# 1_Power_Connector.net
KiCad netlist of a schematic drawn in Altium Designer
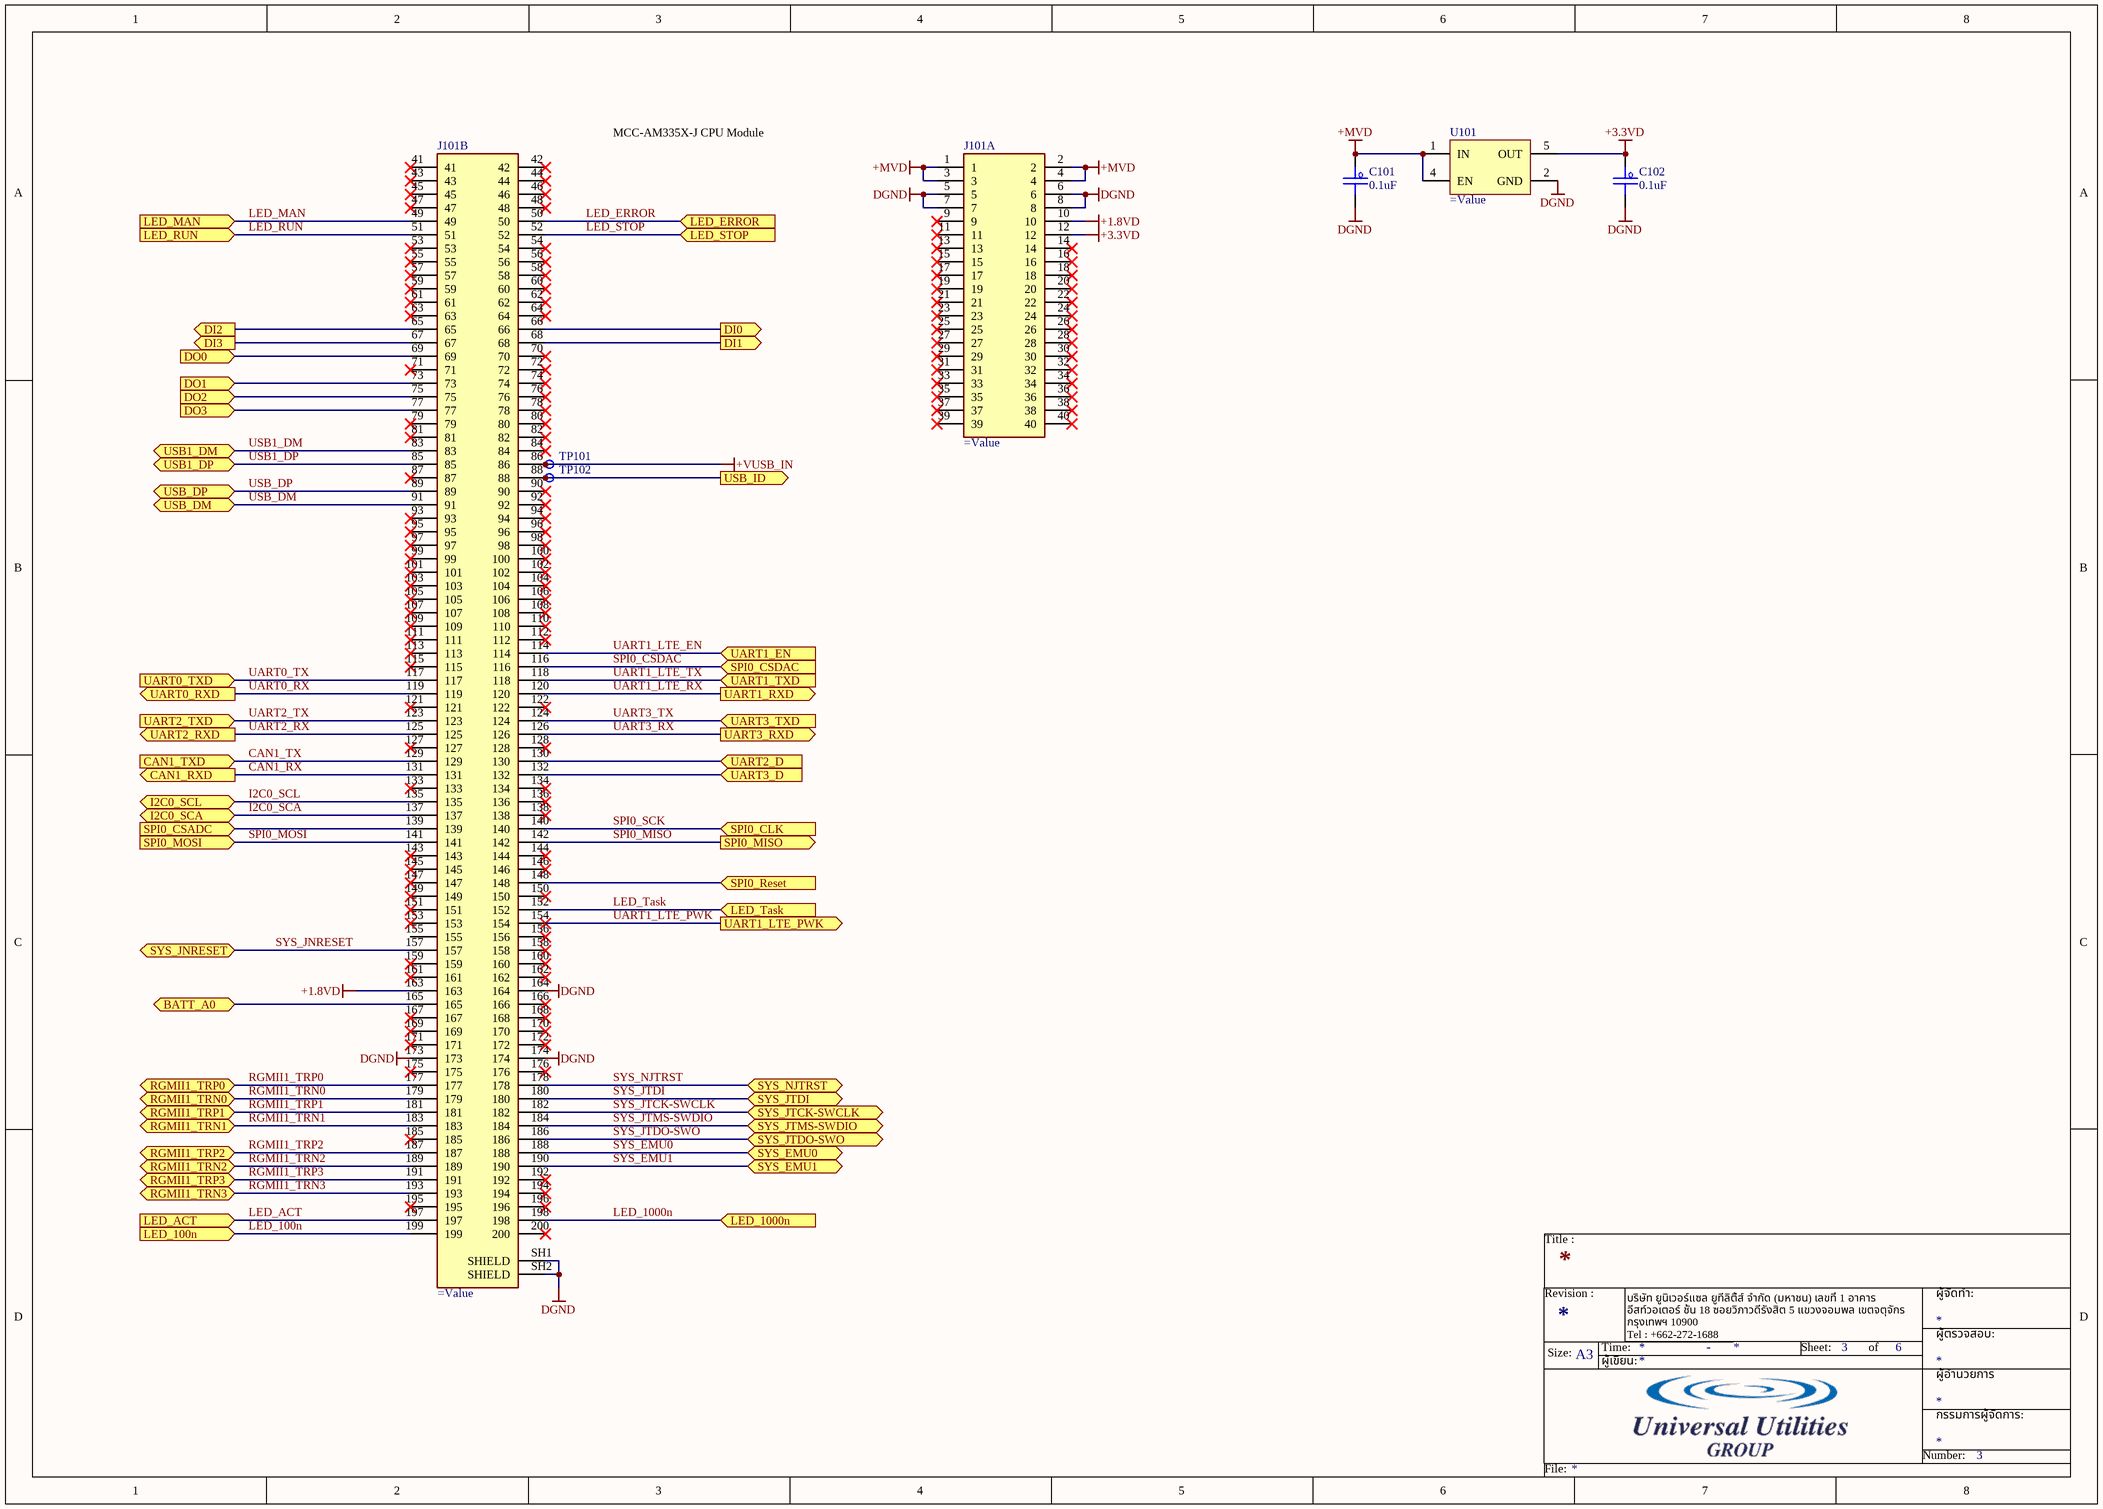
[diagram p0: 1_Power_Connector.SchDoc]

(export (version "E")
  (design (tool "Eeschema 10.0.6"))
  (components
    (comp (ref "C101")
      (value "0.1uF")
      (footprint "C_0603")
      (description "CAP CER 0.1UF 50V X7R 0603")
      (fields (field (name "MANUFACTURER") "KEMET") (field (name "PARTNUMBER") "C0603C104K5RACTU"))
      (libsource (lib "UUSymbol") (part "C_Capacitor"))
    )
    (comp (ref "C102")
      (value "0.1uF")
      (footprint "C_0603")
      (description "CAP CER 0.1UF 50V X7R 0603")
      (fields (field (name "MANUFACTURER") "KEMET") (field (name "PARTNUMBER") "C0603C104K5RACTU"))
      (libsource (lib "UUSymbol") (part "C_Capacitor"))
    )
    (comp (ref "J101")
      (value "~")
      (footprint "DDR2-SO-DIMM")
      (description "CONN SKT SODIMM 200POS R/A SMD")
      (fields
        (field (name "PARTNUMBER") "1473149-4")
        (field (name "MANUFACTURER") "TE Connectivity AMP Connectors")
      )
      (libsource (lib "UUSymbol") (part "CON_DDR2"))
    )
    (comp (ref "TP101")
      (value "~")
      (footprint "TP_Testpoint")
      (description "TestPoint")
      (libsource (lib "UUSymbol") (part "TP_TestPoint"))
    )
    (comp (ref "TP102")
      (value "~")
      (footprint "TP_Testpoint")
      (description "TestPoint")
      (libsource (lib "UUSymbol") (part "TP_TestPoint"))
    )
    (comp (ref "U101")
      (value "~")
      (footprint "SOT95P280X145-5N")
      (description "200mA 360mV@(10mA) Fixed 3.3V~3.3V Positive 1 36V SOT-23-5 Linear Voltage Regulators (LDO) ROHS")
      (fields (field (name "PARTNUMBER") "RT9069-33GB") (field (name "MANUFACTURER") "Richtek Tech"))
      (libsource (lib "UUSymbol") (part "IC_LDO_RT9069-33GB"))
    )
  )
  (nets
    (net (code "1") (name "+1.8VD") (class "Default")
      (node (ref "J101") (pin "10") (pinfunction "10_10") (pintype "passive"))
      (node (ref "J101") (pin "163") (pinfunction "163_163") (pintype "passive"))
    )
    (net (code "2") (name "+3.3VD") (class "Default")
      (node (ref "C102") (pin "1") (pinfunction "1_1") (pintype "passive"))
      (node (ref "J101") (pin "12") (pinfunction "12_12") (pintype "passive"))
      (node (ref "U101") (pin "5") (pinfunction "OUT_5") (pintype "passive"))
    )
    (net (code "3") (name "+MVD") (class "Default")
      (node (ref "C101") (pin "1") (pinfunction "1_1") (pintype "passive"))
      (node (ref "J101") (pin "1") (pinfunction "1_1") (pintype "passive"))
      (node (ref "J101") (pin "2") (pinfunction "2_2") (pintype "passive"))
      (node (ref "J101") (pin "3") (pinfunction "3_3") (pintype "passive"))
      (node (ref "J101") (pin "4") (pinfunction "4_4") (pintype "passive"))
      (node (ref "U101") (pin "1") (pinfunction "IN_1") (pintype "passive"))
      (node (ref "U101") (pin "4") (pinfunction "EN_4") (pintype "passive"))
    )
    (net (code "4") (name "+VUSB_IN") (class "Default")
      (node (ref "J101") (pin "86") (pinfunction "86_86") (pintype "passive"))
      (node (ref "TP101") (pin "1") (pinfunction "1_1") (pintype "passive"))
    )
    (net (code "5") (name "/BATT_A0") (class "Default")
      (node (ref "J101") (pin "165") (pinfunction "165_165") (pintype "passive"))
    )
    (net (code "6") (name "/CAN1_RX") (class "Default")
      (node (ref "J101") (pin "131") (pinfunction "131_131") (pintype "passive"))
    )
    (net (code "7") (name "/CAN1_TX") (class "Default")
      (node (ref "J101") (pin "129") (pinfunction "129_129") (pintype "passive"))
    )
    (net (code "8") (name "/DI0") (class "Default")
      (node (ref "J101") (pin "66") (pinfunction "66_66") (pintype "passive"))
    )
    (net (code "9") (name "/DI1") (class "Default")
      (node (ref "J101") (pin "68") (pinfunction "68_68") (pintype "passive"))
    )
    (net (code "10") (name "/DI2") (class "Default")
      (node (ref "J101") (pin "65") (pinfunction "65_65") (pintype "passive"))
    )
    (net (code "11") (name "/DI3") (class "Default")
      (node (ref "J101") (pin "67") (pinfunction "67_67") (pintype "passive"))
    )
    (net (code "12") (name "/DO0") (class "Default")
      (node (ref "J101") (pin "69") (pinfunction "69_69") (pintype "passive"))
    )
    (net (code "13") (name "/DO1") (class "Default")
      (node (ref "J101") (pin "73") (pinfunction "73_73") (pintype "passive"))
    )
    (net (code "14") (name "/DO2") (class "Default")
      (node (ref "J101") (pin "75") (pinfunction "75_75") (pintype "passive"))
    )
    (net (code "15") (name "/DO3") (class "Default")
      (node (ref "J101") (pin "77") (pinfunction "77_77") (pintype "passive"))
    )
    (net (code "16") (name "/I2C0_SCA") (class "Default")
      (node (ref "J101") (pin "137") (pinfunction "137_137") (pintype "passive"))
    )
    (net (code "17") (name "/I2C0_SCL") (class "Default")
      (node (ref "J101") (pin "135") (pinfunction "135_135") (pintype "passive"))
    )
    (net (code "18") (name "/LED_100n") (class "Default")
      (node (ref "J101") (pin "199") (pinfunction "199_199") (pintype "passive"))
    )
    (net (code "19") (name "/LED_1000n") (class "Default")
      (node (ref "J101") (pin "198") (pinfunction "198_198") (pintype "passive"))
    )
    (net (code "20") (name "/LED_ACT") (class "Default")
      (node (ref "J101") (pin "197") (pinfunction "197_197") (pintype "passive"))
    )
    (net (code "21") (name "/LED_ERROR") (class "Default")
      (node (ref "J101") (pin "50") (pinfunction "50_50") (pintype "passive"))
    )
    (net (code "22") (name "/LED_MAN") (class "Default")
      (node (ref "J101") (pin "49") (pinfunction "49_49") (pintype "passive"))
    )
    (net (code "23") (name "/LED_RUN") (class "Default")
      (node (ref "J101") (pin "51") (pinfunction "51_51") (pintype "passive"))
    )
    (net (code "24") (name "/LED_STOP") (class "Default")
      (node (ref "J101") (pin "52") (pinfunction "52_52") (pintype "passive"))
    )
    (net (code "25") (name "/LED_Task") (class "Default")
      (node (ref "J101") (pin "152") (pinfunction "152_152") (pintype "passive"))
    )
    (net (code "26") (name "/RGMII1_TRN0") (class "Default")
      (node (ref "J101") (pin "179") (pinfunction "179_179") (pintype "passive"))
    )
    (net (code "27") (name "/RGMII1_TRN1") (class "Default")
      (node (ref "J101") (pin "183") (pinfunction "183_183") (pintype "passive"))
    )
    (net (code "28") (name "/RGMII1_TRN2") (class "Default")
      (node (ref "J101") (pin "189") (pinfunction "189_189") (pintype "passive"))
    )
    (net (code "29") (name "/RGMII1_TRN3") (class "Default")
      (node (ref "J101") (pin "193") (pinfunction "193_193") (pintype "passive"))
    )
    (net (code "30") (name "/RGMII1_TRP0") (class "Default")
      (node (ref "J101") (pin "177") (pinfunction "177_177") (pintype "passive"))
    )
    (net (code "31") (name "/RGMII1_TRP1") (class "Default")
      (node (ref "J101") (pin "181") (pinfunction "181_181") (pintype "passive"))
    )
    (net (code "32") (name "/RGMII1_TRP2") (class "Default")
      (node (ref "J101") (pin "187") (pinfunction "187_187") (pintype "passive"))
    )
    (net (code "33") (name "/RGMII1_TRP3") (class "Default")
      (node (ref "J101") (pin "191") (pinfunction "191_191") (pintype "passive"))
    )
    (net (code "34") (name "/SPI0_CSADC") (class "Default")
      (node (ref "J101") (pin "139") (pinfunction "139_139") (pintype "passive"))
    )
    (net (code "35") (name "/SPI0_CSDAC") (class "Default")
      (node (ref "J101") (pin "116") (pinfunction "116_116") (pintype "passive"))
    )
    (net (code "36") (name "/SPI0_MISO") (class "Default")
      (node (ref "J101") (pin "142") (pinfunction "142_142") (pintype "passive"))
    )
    (net (code "37") (name "/SPI0_MOSI") (class "Default")
      (node (ref "J101") (pin "141") (pinfunction "141_141") (pintype "passive"))
    )
    (net (code "38") (name "/SPI0_Reset") (class "Default")
      (node (ref "J101") (pin "148") (pinfunction "148_148") (pintype "passive"))
    )
    (net (code "39") (name "/SPI0_SCK") (class "Default")
      (node (ref "J101") (pin "140") (pinfunction "140_140") (pintype "passive"))
    )
    (net (code "40") (name "/SYS_EMU0") (class "Default")
      (node (ref "J101") (pin "188") (pinfunction "188_188") (pintype "passive"))
    )
    (net (code "41") (name "/SYS_EMU1") (class "Default")
      (node (ref "J101") (pin "190") (pinfunction "190_190") (pintype "passive"))
    )
    (net (code "42") (name "/SYS_JNRESET") (class "Default")
      (node (ref "J101") (pin "157") (pinfunction "157_157") (pintype "passive"))
    )
    (net (code "43") (name "/SYS_JTCK-SWCLK") (class "Default")
      (node (ref "J101") (pin "182") (pinfunction "182_182") (pintype "passive"))
    )
    (net (code "44") (name "/SYS_JTDI") (class "Default")
      (node (ref "J101") (pin "180") (pinfunction "180_180") (pintype "passive"))
    )
    (net (code "45") (name "/SYS_JTDO-SWO") (class "Default")
      (node (ref "J101") (pin "186") (pinfunction "186_186") (pintype "passive"))
    )
    (net (code "46") (name "/SYS_JTMS-SWDIO") (class "Default")
      (node (ref "J101") (pin "184") (pinfunction "184_184") (pintype "passive"))
    )
    (net (code "47") (name "/SYS_NJTRST") (class "Default")
      (node (ref "J101") (pin "178") (pinfunction "178_178") (pintype "passive"))
    )
    (net (code "48") (name "/UART0_RX") (class "Default")
      (node (ref "J101") (pin "119") (pinfunction "119_119") (pintype "passive"))
    )
    (net (code "49") (name "/UART0_TX") (class "Default")
      (node (ref "J101") (pin "117") (pinfunction "117_117") (pintype "passive"))
    )
    (net (code "50") (name "/UART1_LTE_EN") (class "Default")
      (node (ref "J101") (pin "114") (pinfunction "114_114") (pintype "passive"))
    )
    (net (code "51") (name "/UART1_LTE_PWK") (class "Default")
      (node (ref "J101") (pin "154") (pinfunction "154_154") (pintype "passive+no_connect"))
    )
    (net (code "52") (name "/UART1_LTE_RX") (class "Default")
      (node (ref "J101") (pin "120") (pinfunction "120_120") (pintype "passive"))
    )
    (net (code "53") (name "/UART1_LTE_TX") (class "Default")
      (node (ref "J101") (pin "118") (pinfunction "118_118") (pintype "passive"))
    )
    (net (code "54") (name "/UART2_D") (class "Default")
      (node (ref "J101") (pin "130") (pinfunction "130_130") (pintype "passive"))
    )
    (net (code "55") (name "/UART2_RX") (class "Default")
      (node (ref "J101") (pin "125") (pinfunction "125_125") (pintype "passive"))
    )
    (net (code "56") (name "/UART2_TX") (class "Default")
      (node (ref "J101") (pin "123") (pinfunction "123_123") (pintype "passive"))
    )
    (net (code "57") (name "/UART3_D") (class "Default")
      (node (ref "J101") (pin "132") (pinfunction "132_132") (pintype "passive"))
    )
    (net (code "58") (name "/UART3_RX") (class "Default")
      (node (ref "J101") (pin "126") (pinfunction "126_126") (pintype "passive"))
    )
    (net (code "59") (name "/UART3_TX") (class "Default")
      (node (ref "J101") (pin "124") (pinfunction "124_124") (pintype "passive"))
    )
    (net (code "60") (name "/USB1_DM") (class "Default")
      (node (ref "J101") (pin "83") (pinfunction "83_83") (pintype "passive"))
    )
    (net (code "61") (name "/USB1_DP") (class "Default")
      (node (ref "J101") (pin "85") (pinfunction "85_85") (pintype "passive"))
    )
    (net (code "62") (name "/USB_DM") (class "Default")
      (node (ref "J101") (pin "91") (pinfunction "91_91") (pintype "passive"))
    )
    (net (code "63") (name "/USB_DP") (class "Default")
      (node (ref "J101") (pin "89") (pinfunction "89_89") (pintype "passive"))
    )
    (net (code "64") (name "/USB_ID") (class "Default")
      (node (ref "J101") (pin "88") (pinfunction "88_88") (pintype "passive"))
      (node (ref "TP102") (pin "1") (pinfunction "1_1") (pintype "passive"))
    )
    (net (code "65") (name "DGND") (class "Default")
      (node (ref "C101") (pin "2") (pinfunction "2_2") (pintype "passive"))
      (node (ref "C102") (pin "2") (pinfunction "2_2") (pintype "passive"))
      (node (ref "J101") (pin "164") (pinfunction "164_164") (pintype "passive"))
      (node (ref "J101") (pin "173") (pinfunction "173_173") (pintype "passive"))
      (node (ref "J101") (pin "174") (pinfunction "174_174") (pintype "passive"))
      (node (ref "J101") (pin "5") (pinfunction "5_5") (pintype "passive"))
      (node (ref "J101") (pin "6") (pinfunction "6_6") (pintype "passive"))
      (node (ref "J101") (pin "7") (pinfunction "7_7") (pintype "passive"))
      (node (ref "J101") (pin "8") (pinfunction "8_8") (pintype "passive"))
      (node (ref "J101") (pin "SH1") (pinfunction "SHIELD_SH1") (pintype "passive"))
      (node (ref "J101") (pin "SH2") (pinfunction "SHIELD_SH2") (pintype "passive"))
      (node (ref "U101") (pin "2") (pinfunction "GND_2") (pintype "passive"))
    )
    (net (code "66") (name "unconnected-(J101-Pad9)") (class "Default")
      (node (ref "J101") (pin "9") (pinfunction "9_9") (pintype "passive+no_connect"))
    )
    (net (code "67") (name "unconnected-(J101-Pad11)") (class "Default")
      (node (ref "J101") (pin "11") (pinfunction "11_11") (pintype "passive+no_connect"))
    )
    (net (code "68") (name "unconnected-(J101-Pad13)") (class "Default")
      (node (ref "J101") (pin "13") (pinfunction "13_13") (pintype "passive+no_connect"))
    )
    (net (code "69") (name "unconnected-(J101-Pad14)") (class "Default")
      (node (ref "J101") (pin "14") (pinfunction "14_14") (pintype "passive+no_connect"))
    )
    (net (code "70") (name "unconnected-(J101-Pad15)") (class "Default")
      (node (ref "J101") (pin "15") (pinfunction "15_15") (pintype "passive+no_connect"))
    )
    (net (code "71") (name "unconnected-(J101-Pad16)") (class "Default")
      (node (ref "J101") (pin "16") (pinfunction "16_16") (pintype "passive+no_connect"))
    )
    (net (code "72") (name "unconnected-(J101-Pad17)") (class "Default")
      (node (ref "J101") (pin "17") (pinfunction "17_17") (pintype "passive+no_connect"))
    )
    (net (code "73") (name "unconnected-(J101-Pad18)") (class "Default")
      (node (ref "J101") (pin "18") (pinfunction "18_18") (pintype "passive+no_connect"))
    )
    (net (code "74") (name "unconnected-(J101-Pad19)") (class "Default")
      (node (ref "J101") (pin "19") (pinfunction "19_19") (pintype "passive+no_connect"))
    )
    (net (code "75") (name "unconnected-(J101-Pad20)") (class "Default")
      (node (ref "J101") (pin "20") (pinfunction "20_20") (pintype "passive+no_connect"))
    )
    (net (code "76") (name "unconnected-(J101-Pad21)") (class "Default")
      (node (ref "J101") (pin "21") (pinfunction "21_21") (pintype "passive+no_connect"))
    )
    (net (code "77") (name "unconnected-(J101-Pad22)") (class "Default")
      (node (ref "J101") (pin "22") (pinfunction "22_22") (pintype "passive+no_connect"))
    )
    (net (code "78") (name "unconnected-(J101-Pad23)") (class "Default")
      (node (ref "J101") (pin "23") (pinfunction "23_23") (pintype "passive+no_connect"))
    )
    (net (code "79") (name "unconnected-(J101-Pad24)") (class "Default")
      (node (ref "J101") (pin "24") (pinfunction "24_24") (pintype "passive+no_connect"))
    )
    (net (code "80") (name "unconnected-(J101-Pad25)") (class "Default")
      (node (ref "J101") (pin "25") (pinfunction "25_25") (pintype "passive+no_connect"))
    )
    (net (code "81") (name "unconnected-(J101-Pad26)") (class "Default")
      (node (ref "J101") (pin "26") (pinfunction "26_26") (pintype "passive+no_connect"))
    )
    (net (code "82") (name "unconnected-(J101-Pad27)") (class "Default")
      (node (ref "J101") (pin "27") (pinfunction "27_27") (pintype "passive+no_connect"))
    )
    (net (code "83") (name "unconnected-(J101-Pad28)") (class "Default")
      (node (ref "J101") (pin "28") (pinfunction "28_28") (pintype "passive+no_connect"))
    )
    (net (code "84") (name "unconnected-(J101-Pad29)") (class "Default")
      (node (ref "J101") (pin "29") (pinfunction "29_29") (pintype "passive+no_connect"))
    )
    (net (code "85") (name "unconnected-(J101-Pad30)") (class "Default")
      (node (ref "J101") (pin "30") (pinfunction "30_30") (pintype "passive+no_connect"))
    )
    (net (code "86") (name "unconnected-(J101-Pad31)") (class "Default")
      (node (ref "J101") (pin "31") (pinfunction "31_31") (pintype "passive+no_connect"))
    )
    (net (code "87") (name "unconnected-(J101-Pad32)") (class "Default")
      (node (ref "J101") (pin "32") (pinfunction "32_32") (pintype "passive+no_connect"))
    )
    (net (code "88") (name "unconnected-(J101-Pad33)") (class "Default")
      (node (ref "J101") (pin "33") (pinfunction "33_33") (pintype "passive+no_connect"))
    )
    (net (code "89") (name "unconnected-(J101-Pad34)") (class "Default")
      (node (ref "J101") (pin "34") (pinfunction "34_34") (pintype "passive+no_connect"))
    )
    (net (code "90") (name "unconnected-(J101-Pad35)") (class "Default")
      (node (ref "J101") (pin "35") (pinfunction "35_35") (pintype "passive+no_connect"))
    )
    (net (code "91") (name "unconnected-(J101-Pad36)") (class "Default")
      (node (ref "J101") (pin "36") (pinfunction "36_36") (pintype "passive+no_connect"))
    )
    (net (code "92") (name "unconnected-(J101-Pad37)") (class "Default")
      (node (ref "J101") (pin "37") (pinfunction "37_37") (pintype "passive+no_connect"))
    )
    (net (code "93") (name "unconnected-(J101-Pad38)") (class "Default")
      (node (ref "J101") (pin "38") (pinfunction "38_38") (pintype "passive+no_connect"))
    )
    (net (code "94") (name "unconnected-(J101-Pad39)") (class "Default")
      (node (ref "J101") (pin "39") (pinfunction "39_39") (pintype "passive+no_connect"))
    )
    (net (code "95") (name "unconnected-(J101-Pad40)") (class "Default")
      (node (ref "J101") (pin "40") (pinfunction "40_40") (pintype "passive+no_connect"))
    )
    (net (code "96") (name "unconnected-(J101-Pad41)") (class "Default")
      (node (ref "J101") (pin "41") (pinfunction "41_41") (pintype "passive+no_connect"))
    )
    (net (code "97") (name "unconnected-(J101-Pad42)") (class "Default")
      (node (ref "J101") (pin "42") (pinfunction "42_42") (pintype "passive+no_connect"))
    )
    (net (code "98") (name "unconnected-(J101-Pad43)") (class "Default")
      (node (ref "J101") (pin "43") (pinfunction "43_43") (pintype "passive+no_connect"))
    )
    (net (code "99") (name "unconnected-(J101-Pad44)") (class "Default")
      (node (ref "J101") (pin "44") (pinfunction "44_44") (pintype "passive+no_connect"))
    )
    (net (code "100") (name "unconnected-(J101-Pad45)") (class "Default")
      (node (ref "J101") (pin "45") (pinfunction "45_45") (pintype "passive+no_connect"))
    )
    (net (code "101") (name "unconnected-(J101-Pad46)") (class "Default")
      (node (ref "J101") (pin "46") (pinfunction "46_46") (pintype "passive+no_connect"))
    )
    (net (code "102") (name "unconnected-(J101-Pad47)") (class "Default")
      (node (ref "J101") (pin "47") (pinfunction "47_47") (pintype "passive+no_connect"))
    )
    (net (code "103") (name "unconnected-(J101-Pad48)") (class "Default")
      (node (ref "J101") (pin "48") (pinfunction "48_48") (pintype "passive+no_connect"))
    )
    (net (code "104") (name "unconnected-(J101-Pad53)") (class "Default")
      (node (ref "J101") (pin "53") (pinfunction "53_53") (pintype "passive+no_connect"))
    )
    (net (code "105") (name "unconnected-(J101-Pad54)") (class "Default")
      (node (ref "J101") (pin "54") (pinfunction "54_54") (pintype "passive+no_connect"))
    )
    (net (code "106") (name "unconnected-(J101-Pad55)") (class "Default")
      (node (ref "J101") (pin "55") (pinfunction "55_55") (pintype "passive+no_connect"))
    )
    (net (code "107") (name "unconnected-(J101-Pad56)") (class "Default")
      (node (ref "J101") (pin "56") (pinfunction "56_56") (pintype "passive+no_connect"))
    )
    (net (code "108") (name "unconnected-(J101-Pad57)") (class "Default")
      (node (ref "J101") (pin "57") (pinfunction "57_57") (pintype "passive+no_connect"))
    )
    (net (code "109") (name "unconnected-(J101-Pad58)") (class "Default")
      (node (ref "J101") (pin "58") (pinfunction "58_58") (pintype "passive+no_connect"))
    )
    (net (code "110") (name "unconnected-(J101-Pad59)") (class "Default")
      (node (ref "J101") (pin "59") (pinfunction "59_59") (pintype "passive+no_connect"))
    )
    (net (code "111") (name "unconnected-(J101-Pad60)") (class "Default")
      (node (ref "J101") (pin "60") (pinfunction "60_60") (pintype "passive+no_connect"))
    )
    (net (code "112") (name "unconnected-(J101-Pad61)") (class "Default")
      (node (ref "J101") (pin "61") (pinfunction "61_61") (pintype "passive+no_connect"))
    )
    (net (code "113") (name "unconnected-(J101-Pad62)") (class "Default")
      (node (ref "J101") (pin "62") (pinfunction "62_62") (pintype "passive+no_connect"))
    )
    (net (code "114") (name "unconnected-(J101-Pad63)") (class "Default")
      (node (ref "J101") (pin "63") (pinfunction "63_63") (pintype "passive+no_connect"))
    )
    (net (code "115") (name "unconnected-(J101-Pad64)") (class "Default")
      (node (ref "J101") (pin "64") (pinfunction "64_64") (pintype "passive+no_connect"))
    )
    (net (code "116") (name "unconnected-(J101-Pad70)") (class "Default")
      (node (ref "J101") (pin "70") (pinfunction "70_70") (pintype "passive+no_connect"))
    )
    (net (code "117") (name "unconnected-(J101-Pad71)") (class "Default")
      (node (ref "J101") (pin "71") (pinfunction "71_71") (pintype "passive+no_connect"))
    )
    (net (code "118") (name "unconnected-(J101-Pad72)") (class "Default")
      (node (ref "J101") (pin "72") (pinfunction "72_72") (pintype "passive+no_connect"))
    )
    (net (code "119") (name "unconnected-(J101-Pad74)") (class "Default")
      (node (ref "J101") (pin "74") (pinfunction "74_74") (pintype "passive+no_connect"))
    )
    (net (code "120") (name "unconnected-(J101-Pad76)") (class "Default")
      (node (ref "J101") (pin "76") (pinfunction "76_76") (pintype "passive+no_connect"))
    )
    (net (code "121") (name "unconnected-(J101-Pad78)") (class "Default")
      (node (ref "J101") (pin "78") (pinfunction "78_78") (pintype "passive+no_connect"))
    )
    (net (code "122") (name "unconnected-(J101-Pad79)") (class "Default")
      (node (ref "J101") (pin "79") (pinfunction "79_79") (pintype "passive+no_connect"))
    )
    (net (code "123") (name "unconnected-(J101-Pad80)") (class "Default")
      (node (ref "J101") (pin "80") (pinfunction "80_80") (pintype "passive+no_connect"))
    )
    (net (code "124") (name "unconnected-(J101-Pad81)") (class "Default")
      (node (ref "J101") (pin "81") (pinfunction "81_81") (pintype "passive+no_connect"))
    )
    (net (code "125") (name "unconnected-(J101-Pad82)") (class "Default")
      (node (ref "J101") (pin "82") (pinfunction "82_82") (pintype "passive+no_connect"))
    )
    (net (code "126") (name "unconnected-(J101-Pad84)") (class "Default")
      (node (ref "J101") (pin "84") (pinfunction "84_84") (pintype "passive+no_connect"))
    )
    (net (code "127") (name "unconnected-(J101-Pad87)") (class "Default")
      (node (ref "J101") (pin "87") (pinfunction "87_87") (pintype "passive+no_connect"))
    )
    (net (code "128") (name "unconnected-(J101-Pad90)") (class "Default")
      (node (ref "J101") (pin "90") (pinfunction "90_90") (pintype "passive+no_connect"))
    )
    (net (code "129") (name "unconnected-(J101-Pad92)") (class "Default")
      (node (ref "J101") (pin "92") (pinfunction "92_92") (pintype "passive+no_connect"))
    )
    (net (code "130") (name "unconnected-(J101-Pad93)") (class "Default")
      (node (ref "J101") (pin "93") (pinfunction "93_93") (pintype "passive+no_connect"))
    )
    (net (code "131") (name "unconnected-(J101-Pad94)") (class "Default")
      (node (ref "J101") (pin "94") (pinfunction "94_94") (pintype "passive+no_connect"))
    )
    (net (code "132") (name "unconnected-(J101-Pad95)") (class "Default")
      (node (ref "J101") (pin "95") (pinfunction "95_95") (pintype "passive+no_connect"))
    )
    (net (code "133") (name "unconnected-(J101-Pad96)") (class "Default")
      (node (ref "J101") (pin "96") (pinfunction "96_96") (pintype "passive+no_connect"))
    )
    (net (code "134") (name "unconnected-(J101-Pad97)") (class "Default")
      (node (ref "J101") (pin "97") (pinfunction "97_97") (pintype "passive+no_connect"))
    )
    (net (code "135") (name "unconnected-(J101-Pad98)") (class "Default")
      (node (ref "J101") (pin "98") (pinfunction "98_98") (pintype "passive+no_connect"))
    )
    (net (code "136") (name "unconnected-(J101-Pad99)") (class "Default")
      (node (ref "J101") (pin "99") (pinfunction "99_99") (pintype "passive+no_connect"))
    )
    (net (code "137") (name "unconnected-(J101-Pad100)") (class "Default")
      (node (ref "J101") (pin "100") (pinfunction "100_100") (pintype "passive+no_connect"))
    )
    (net (code "138") (name "unconnected-(J101-Pad101)") (class "Default")
      (node (ref "J101") (pin "101") (pinfunction "101_101") (pintype "passive+no_connect"))
    )
    (net (code "139") (name "unconnected-(J101-Pad102)") (class "Default")
      (node (ref "J101") (pin "102") (pinfunction "102_102") (pintype "passive+no_connect"))
    )
    (net (code "140") (name "unconnected-(J101-Pad103)") (class "Default")
      (node (ref "J101") (pin "103") (pinfunction "103_103") (pintype "passive+no_connect"))
    )
    (net (code "141") (name "unconnected-(J101-Pad104)") (class "Default")
      (node (ref "J101") (pin "104") (pinfunction "104_104") (pintype "passive+no_connect"))
    )
    (net (code "142") (name "unconnected-(J101-Pad105)") (class "Default")
      (node (ref "J101") (pin "105") (pinfunction "105_105") (pintype "passive+no_connect"))
    )
    (net (code "143") (name "unconnected-(J101-Pad106)") (class "Default")
      (node (ref "J101") (pin "106") (pinfunction "106_106") (pintype "passive+no_connect"))
    )
    (net (code "144") (name "unconnected-(J101-Pad107)") (class "Default")
      (node (ref "J101") (pin "107") (pinfunction "107_107") (pintype "passive+no_connect"))
    )
    (net (code "145") (name "unconnected-(J101-Pad108)") (class "Default")
      (node (ref "J101") (pin "108") (pinfunction "108_108") (pintype "passive+no_connect"))
    )
    (net (code "146") (name "unconnected-(J101-Pad109)") (class "Default")
      (node (ref "J101") (pin "109") (pinfunction "109_109") (pintype "passive+no_connect"))
    )
    (net (code "147") (name "unconnected-(J101-Pad110)") (class "Default")
      (node (ref "J101") (pin "110") (pinfunction "110_110") (pintype "passive+no_connect"))
    )
    (net (code "148") (name "unconnected-(J101-Pad111)") (class "Default")
      (node (ref "J101") (pin "111") (pinfunction "111_111") (pintype "passive+no_connect"))
    )
    (net (code "149") (name "unconnected-(J101-Pad112)") (class "Default")
      (node (ref "J101") (pin "112") (pinfunction "112_112") (pintype "passive+no_connect"))
    )
    (net (code "150") (name "unconnected-(J101-Pad113)") (class "Default")
      (node (ref "J101") (pin "113") (pinfunction "113_113") (pintype "passive+no_connect"))
    )
    (net (code "151") (name "unconnected-(J101-Pad115)") (class "Default")
      (node (ref "J101") (pin "115") (pinfunction "115_115") (pintype "passive+no_connect"))
    )
    (net (code "152") (name "unconnected-(J101-Pad121)") (class "Default")
      (node (ref "J101") (pin "121") (pinfunction "121_121") (pintype "passive+no_connect"))
    )
    (net (code "153") (name "unconnected-(J101-Pad122)") (class "Default")
      (node (ref "J101") (pin "122") (pinfunction "122_122") (pintype "passive+no_connect"))
    )
    (net (code "154") (name "unconnected-(J101-Pad127)") (class "Default")
      (node (ref "J101") (pin "127") (pinfunction "127_127") (pintype "passive+no_connect"))
    )
    (net (code "155") (name "unconnected-(J101-Pad128)") (class "Default")
      (node (ref "J101") (pin "128") (pinfunction "128_128") (pintype "passive+no_connect"))
    )
    (net (code "156") (name "unconnected-(J101-Pad133)") (class "Default")
      (node (ref "J101") (pin "133") (pinfunction "133_133") (pintype "passive+no_connect"))
    )
    (net (code "157") (name "unconnected-(J101-Pad134)") (class "Default")
      (node (ref "J101") (pin "134") (pinfunction "134_134") (pintype "passive+no_connect"))
    )
    (net (code "158") (name "unconnected-(J101-Pad136)") (class "Default")
      (node (ref "J101") (pin "136") (pinfunction "136_136") (pintype "passive+no_connect"))
    )
    (net (code "159") (name "unconnected-(J101-Pad138)") (class "Default")
      (node (ref "J101") (pin "138") (pinfunction "138_138") (pintype "passive+no_connect"))
    )
    (net (code "160") (name "unconnected-(J101-Pad143)") (class "Default")
      (node (ref "J101") (pin "143") (pinfunction "143_143") (pintype "passive+no_connect"))
    )
    (net (code "161") (name "unconnected-(J101-Pad144)") (class "Default")
      (node (ref "J101") (pin "144") (pinfunction "144_144") (pintype "passive+no_connect"))
    )
    (net (code "162") (name "unconnected-(J101-Pad145)") (class "Default")
      (node (ref "J101") (pin "145") (pinfunction "145_145") (pintype "passive+no_connect"))
    )
    (net (code "163") (name "unconnected-(J101-Pad146)") (class "Default")
      (node (ref "J101") (pin "146") (pinfunction "146_146") (pintype "passive+no_connect"))
    )
    (net (code "164") (name "unconnected-(J101-Pad147)") (class "Default")
      (node (ref "J101") (pin "147") (pinfunction "147_147") (pintype "passive+no_connect"))
    )
    (net (code "165") (name "unconnected-(J101-Pad149)") (class "Default")
      (node (ref "J101") (pin "149") (pinfunction "149_149") (pintype "passive+no_connect"))
    )
    (net (code "166") (name "unconnected-(J101-Pad150)") (class "Default")
      (node (ref "J101") (pin "150") (pinfunction "150_150") (pintype "passive+no_connect"))
    )
    (net (code "167") (name "unconnected-(J101-Pad151)") (class "Default")
      (node (ref "J101") (pin "151") (pinfunction "151_151") (pintype "passive+no_connect"))
    )
    (net (code "168") (name "unconnected-(J101-Pad153)") (class "Default")
      (node (ref "J101") (pin "153") (pinfunction "153_153") (pintype "passive+no_connect"))
    )
    (net (code "169") (name "unconnected-(J101-Pad155)") (class "Default")
      (node (ref "J101") (pin "155") (pinfunction "155_155") (pintype "passive"))
    )
    (net (code "170") (name "unconnected-(J101-Pad156)") (class "Default")
      (node (ref "J101") (pin "156") (pinfunction "156_156") (pintype "passive+no_connect"))
    )
    (net (code "171") (name "unconnected-(J101-Pad158)") (class "Default")
      (node (ref "J101") (pin "158") (pinfunction "158_158") (pintype "passive+no_connect"))
    )
    (net (code "172") (name "unconnected-(J101-Pad159)") (class "Default")
      (node (ref "J101") (pin "159") (pinfunction "159_159") (pintype "passive+no_connect"))
    )
    (net (code "173") (name "unconnected-(J101-Pad160)") (class "Default")
      (node (ref "J101") (pin "160") (pinfunction "160_160") (pintype "passive+no_connect"))
    )
    (net (code "174") (name "unconnected-(J101-Pad161)") (class "Default")
      (node (ref "J101") (pin "161") (pinfunction "161_161") (pintype "passive+no_connect"))
    )
    (net (code "175") (name "unconnected-(J101-Pad162)") (class "Default")
      (node (ref "J101") (pin "162") (pinfunction "162_162") (pintype "passive+no_connect"))
    )
    (net (code "176") (name "unconnected-(J101-Pad166)") (class "Default")
      (node (ref "J101") (pin "166") (pinfunction "166_166") (pintype "passive+no_connect"))
    )
    (net (code "177") (name "unconnected-(J101-Pad167)") (class "Default")
      (node (ref "J101") (pin "167") (pinfunction "167_167") (pintype "passive+no_connect"))
    )
    (net (code "178") (name "unconnected-(J101-Pad168)") (class "Default")
      (node (ref "J101") (pin "168") (pinfunction "168_168") (pintype "passive+no_connect"))
    )
    (net (code "179") (name "unconnected-(J101-Pad169)") (class "Default")
      (node (ref "J101") (pin "169") (pinfunction "169_169") (pintype "passive+no_connect"))
    )
    (net (code "180") (name "unconnected-(J101-Pad170)") (class "Default")
      (node (ref "J101") (pin "170") (pinfunction "170_170") (pintype "passive+no_connect"))
    )
    (net (code "181") (name "unconnected-(J101-Pad171)") (class "Default")
      (node (ref "J101") (pin "171") (pinfunction "171_171") (pintype "passive+no_connect"))
    )
    (net (code "182") (name "unconnected-(J101-Pad172)") (class "Default")
      (node (ref "J101") (pin "172") (pinfunction "172_172") (pintype "passive+no_connect"))
    )
    (net (code "183") (name "unconnected-(J101-Pad175)") (class "Default")
      (node (ref "J101") (pin "175") (pinfunction "175_175") (pintype "passive+no_connect"))
    )
    (net (code "184") (name "unconnected-(J101-Pad176)") (class "Default")
      (node (ref "J101") (pin "176") (pinfunction "176_176") (pintype "passive+no_connect"))
    )
    (net (code "185") (name "unconnected-(J101-Pad185)") (class "Default")
      (node (ref "J101") (pin "185") (pinfunction "185_185") (pintype "passive+no_connect"))
    )
    (net (code "186") (name "unconnected-(J101-Pad192)") (class "Default")
      (node (ref "J101") (pin "192") (pinfunction "192_192") (pintype "passive+no_connect"))
    )
    (net (code "187") (name "unconnected-(J101-Pad194)") (class "Default")
      (node (ref "J101") (pin "194") (pinfunction "194_194") (pintype "passive+no_connect"))
    )
    (net (code "188") (name "unconnected-(J101-Pad195)") (class "Default")
      (node (ref "J101") (pin "195") (pinfunction "195_195") (pintype "passive+no_connect"))
    )
    (net (code "189") (name "unconnected-(J101-Pad196)") (class "Default")
      (node (ref "J101") (pin "196") (pinfunction "196_196") (pintype "passive+no_connect"))
    )
    (net (code "190") (name "unconnected-(J101-Pad200)") (class "Default")
      (node (ref "J101") (pin "200") (pinfunction "200_200") (pintype "passive+no_connect"))
    )
  )
)
